# LEDDimmerDuoMini.net
KiCad netlist of a schematic drawn in EAGLE
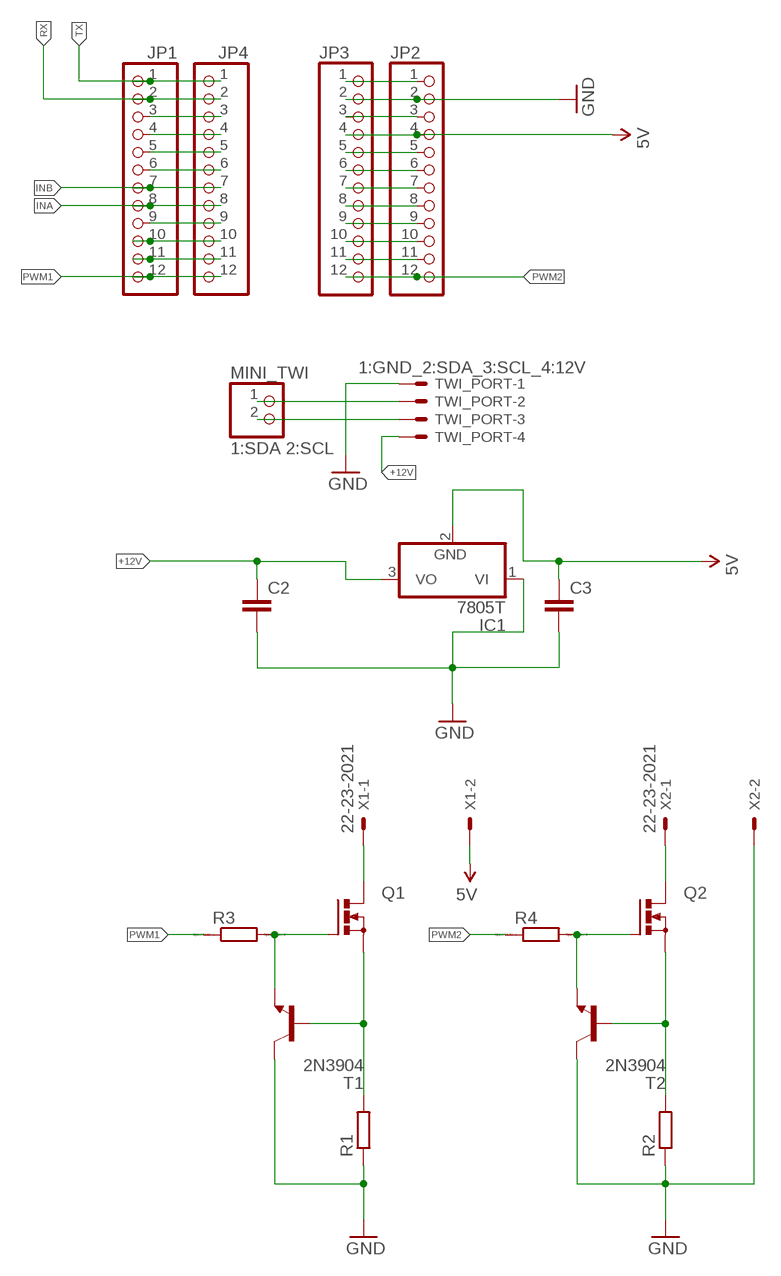
[diagram p0: schematic, sheet 1]

(export (version "E")
  (design (tool "Eeschema 10.0.6"))
  (components
    (comp (ref "C2")
      (value "CAP0603-CAP")
      (footprint "eagle-import:0603-CAP")
      (libsource (lib "eagle-import") (part "CAP0603-CAP"))
    )
    (comp (ref "C3")
      (value "CAP0603-CAP")
      (footprint "eagle-import:0603-CAP")
      (libsource (lib "eagle-import") (part "CAP0603-CAP"))
    )
    (comp (ref "IC1")
      (value "7805T")
      (footprint "eagle-import:TO220H")
      (libsource (lib "eagle-import") (part "78T05"))
    )
    (comp (ref "JP1")
      (value "PINHD-1X12")
      (footprint "eagle-import:1X12")
      (libsource (lib "eagle-import") (part "PINHD-1X12"))
    )
    (comp (ref "JP2")
      (value "PINHD-1X12")
      (footprint "eagle-import:1X12")
      (libsource (lib "eagle-import") (part "PINHD-1X12"))
    )
    (comp (ref "JP3")
      (value "PINHD-1X12")
      (footprint "eagle-import:1X12")
      (libsource (lib "eagle-import") (part "PINHD-1X12"))
    )
    (comp (ref "JP4")
      (value "PINHD-1X12")
      (footprint "eagle-import:1X12")
      (libsource (lib "eagle-import") (part "PINHD-1X12"))
    )
    (comp (ref "MINI_TWI")
      (value "1:SDA 2:SCL")
      (footprint "eagle-import:1X02")
      (libsource (lib "eagle-import") (part "PINHD-1X2"))
    )
    (comp (ref "Q1")
      (value "PMOSFET_NTO220BV")
      (footprint "eagle-import:TO220BV")
      (libsource (lib "eagle-import") (part "PMOSFET_NTO220BV"))
    )
    (comp (ref "Q2")
      (value "PMOSFET_NTO220BV")
      (footprint "eagle-import:TO220BV")
      (libsource (lib "eagle-import") (part "PMOSFET_NTO220BV"))
    )
    (comp (ref "R1")
      (value "R-EU_VTA52")
      (footprint "eagle-import:VTA52")
      (libsource (lib "eagle-import") (part "R-EU_VTA52"))
    )
    (comp (ref "R2")
      (value "R-EU_VTA52")
      (footprint "eagle-import:VTA52")
      (libsource (lib "eagle-import") (part "R-EU_VTA52"))
    )
    (comp (ref "R3") (value "R") (footprint "eagle-import:R0805") (libsource (lib "eagle-import") (part "R")))
    (comp (ref "R4") (value "R") (footprint "eagle-import:R0805") (libsource (lib "eagle-import") (part "R")))
    (comp (ref "T1")
      (value "2N3904")
      (footprint "eagle-import:TO92")
      (libsource (lib "eagle-import") (part "2N3904"))
    )
    (comp (ref "T2")
      (value "2N3904")
      (footprint "eagle-import:TO92")
      (libsource (lib "eagle-import") (part "2N3904"))
    )
    (comp (ref "TWI_PORT")
      (value "1:GND_2:SDA_3:SCL_4:12V")
      (footprint "eagle-import:22-23-2041")
      (fields (field (name "MF") "MOLEX") (field (name "MPN") "22-23-2041"))
      (libsource (lib "eagle-import") (part "22-23-2041"))
    )
    (comp (ref "X1")
      (value "22-23-2021")
      (footprint "eagle-import:22-23-2021")
      (fields (field (name "MF") "MOLEX"))
      (libsource (lib "eagle-import") (part "22-23-2021"))
    )
    (comp (ref "X2")
      (value "22-23-2021")
      (footprint "eagle-import:22-23-2021")
      (fields (field (name "MF") "MOLEX"))
      (libsource (lib "eagle-import") (part "22-23-2021"))
    )
  )
  (nets
    (net (code "1") (name "+12V") (class "Default")
      (node (ref "C2") (pin "1") (pinfunction "1_1") (pintype "passive"))
      (node (ref "IC1") (pin "3") (pinfunction "VO_3") (pintype "passive"))
      (node (ref "TWI_PORT") (pin "4") (pinfunction "S_4") (pintype "passive"))
    )
    (net (code "2") (name "5V") (class "Default")
      (node (ref "C3") (pin "1") (pinfunction "1_1") (pintype "passive"))
      (node (ref "IC1") (pin "2") (pinfunction "GND_2") (pintype "passive"))
      (node (ref "JP2") (pin "4") (pinfunction "4_4") (pintype "passive"))
      (node (ref "JP3") (pin "4") (pinfunction "4_4") (pintype "passive"))
      (node (ref "X1") (pin "2") (pinfunction "S_2") (pintype "passive"))
    )
    (net (code "3") (name "GND") (class "Default")
      (node (ref "C2") (pin "2") (pinfunction "2_2") (pintype "passive"))
      (node (ref "C3") (pin "2") (pinfunction "2_2") (pintype "passive"))
      (node (ref "IC1") (pin "1") (pinfunction "VI_1") (pintype "input"))
      (node (ref "JP2") (pin "2") (pinfunction "2_2") (pintype "passive"))
      (node (ref "JP3") (pin "2") (pinfunction "2_2") (pintype "passive"))
      (node (ref "R1") (pin "1") (pinfunction "1_1") (pintype "passive"))
      (node (ref "R2") (pin "1") (pinfunction "1_1") (pintype "passive"))
      (node (ref "T1") (pin "1") (pinfunction "C_1") (pintype "passive"))
      (node (ref "T2") (pin "1") (pinfunction "C_1") (pintype "passive"))
      (node (ref "TWI_PORT") (pin "1") (pinfunction "S_1") (pintype "passive"))
      (node (ref "X2") (pin "2") (pinfunction "S_2") (pintype "passive"))
    )
    (net (code "4") (name "INA") (class "Default")
      (node (ref "JP1") (pin "8") (pinfunction "8_8") (pintype "passive"))
      (node (ref "JP4") (pin "8") (pinfunction "8_8") (pintype "passive"))
    )
    (net (code "5") (name "INB") (class "Default")
      (node (ref "JP1") (pin "7") (pinfunction "7_7") (pintype "passive"))
      (node (ref "JP4") (pin "7") (pinfunction "7_7") (pintype "passive"))
    )
    (net (code "6") (name "Net-(JP1-Pad3)") (class "Default")
      (node (ref "JP1") (pin "3") (pinfunction "3_3") (pintype "passive"))
      (node (ref "JP4") (pin "3") (pinfunction "3_3") (pintype "passive"))
    )
    (net (code "7") (name "Net-(JP1-Pad4)") (class "Default")
      (node (ref "JP1") (pin "4") (pinfunction "4_4") (pintype "passive"))
      (node (ref "JP4") (pin "4") (pinfunction "4_4") (pintype "passive"))
    )
    (net (code "8") (name "Net-(JP1-Pad5)") (class "Default")
      (node (ref "JP1") (pin "5") (pinfunction "5_5") (pintype "passive"))
      (node (ref "JP4") (pin "5") (pinfunction "5_5") (pintype "passive"))
    )
    (net (code "9") (name "Net-(JP1-Pad6)") (class "Default")
      (node (ref "JP1") (pin "6") (pinfunction "6_6") (pintype "passive"))
      (node (ref "JP4") (pin "6") (pinfunction "6_6") (pintype "passive"))
    )
    (net (code "10") (name "Net-(JP1-Pad9)") (class "Default")
      (node (ref "JP1") (pin "9") (pinfunction "9_9") (pintype "passive"))
      (node (ref "JP4") (pin "9") (pinfunction "9_9") (pintype "passive"))
    )
    (net (code "11") (name "Net-(JP1-Pad10)") (class "Default")
      (node (ref "JP1") (pin "10") (pinfunction "10_10") (pintype "passive"))
      (node (ref "JP4") (pin "10") (pinfunction "10_10") (pintype "passive"))
    )
    (net (code "12") (name "Net-(JP1-Pad11)") (class "Default")
      (node (ref "JP1") (pin "11") (pinfunction "11_11") (pintype "passive"))
      (node (ref "JP4") (pin "11") (pinfunction "11_11") (pintype "passive"))
    )
    (net (code "13") (name "Net-(JP2-Pad1)") (class "Default")
      (node (ref "JP2") (pin "1") (pinfunction "1_1") (pintype "passive"))
      (node (ref "JP3") (pin "1") (pinfunction "1_1") (pintype "passive"))
    )
    (net (code "14") (name "Net-(JP2-Pad3)") (class "Default")
      (node (ref "JP2") (pin "3") (pinfunction "3_3") (pintype "passive"))
      (node (ref "JP3") (pin "3") (pinfunction "3_3") (pintype "passive"))
    )
    (net (code "15") (name "Net-(JP2-Pad5)") (class "Default")
      (node (ref "JP2") (pin "5") (pinfunction "5_5") (pintype "passive"))
      (node (ref "JP3") (pin "5") (pinfunction "5_5") (pintype "passive"))
    )
    (net (code "16") (name "Net-(JP2-Pad6)") (class "Default")
      (node (ref "JP2") (pin "6") (pinfunction "6_6") (pintype "passive"))
      (node (ref "JP3") (pin "6") (pinfunction "6_6") (pintype "passive"))
    )
    (net (code "17") (name "Net-(JP2-Pad7)") (class "Default")
      (node (ref "JP2") (pin "7") (pinfunction "7_7") (pintype "passive"))
      (node (ref "JP3") (pin "7") (pinfunction "7_7") (pintype "passive"))
    )
    (net (code "18") (name "Net-(JP2-Pad8)") (class "Default")
      (node (ref "JP2") (pin "8") (pinfunction "8_8") (pintype "passive"))
      (node (ref "JP3") (pin "8") (pinfunction "8_8") (pintype "passive"))
    )
    (net (code "19") (name "Net-(JP2-Pad9)") (class "Default")
      (node (ref "JP2") (pin "9") (pinfunction "9_9") (pintype "passive"))
      (node (ref "JP3") (pin "9") (pinfunction "9_9") (pintype "passive"))
    )
    (net (code "20") (name "Net-(JP2-Pad10)") (class "Default")
      (node (ref "JP2") (pin "10") (pinfunction "10_10") (pintype "passive"))
      (node (ref "JP3") (pin "10") (pinfunction "10_10") (pintype "passive"))
    )
    (net (code "21") (name "Net-(JP2-Pad11)") (class "Default")
      (node (ref "JP2") (pin "11") (pinfunction "11_11") (pintype "passive"))
      (node (ref "JP3") (pin "11") (pinfunction "11_11") (pintype "passive"))
    )
    (net (code "22") (name "Net-(T1-B)") (class "Default")
      (node (ref "Q1") (pin "S") (pinfunction "S_S") (pintype "passive"))
      (node (ref "R1") (pin "2") (pinfunction "2_2") (pintype "passive"))
      (node (ref "T1") (pin "2") (pinfunction "B_2") (pintype "passive"))
    )
    (net (code "23") (name "Net-(T2-B)") (class "Default")
      (node (ref "Q2") (pin "S") (pinfunction "S_S") (pintype "passive"))
      (node (ref "R2") (pin "2") (pinfunction "2_2") (pintype "passive"))
      (node (ref "T2") (pin "2") (pinfunction "B_2") (pintype "passive"))
    )
    (net (code "24") (name "Net-(T2-E)") (class "Default")
      (node (ref "Q2") (pin "G") (pinfunction "G_G") (pintype "passive"))
      (node (ref "R4") (pin "2") (pinfunction "2_2") (pintype "passive"))
      (node (ref "T2") (pin "3") (pinfunction "E_3") (pintype "passive"))
    )
    (net (code "25") (name "Net-(TWI_PORTB-S)") (class "Default")
      (node (ref "MINI_TWI") (pin "1") (pinfunction "1_1") (pintype "passive"))
      (node (ref "TWI_PORT") (pin "2") (pinfunction "S_2") (pintype "passive"))
    )
    (net (code "26") (name "Net-(TWI_PORTC-S)") (class "Default")
      (node (ref "MINI_TWI") (pin "2") (pinfunction "2_2") (pintype "passive"))
      (node (ref "TWI_PORT") (pin "3") (pinfunction "S_3") (pintype "passive"))
    )
    (net (code "27") (name "Net-(X1A-S)") (class "Default")
      (node (ref "Q1") (pin "D") (pinfunction "D_D") (pintype "passive"))
      (node (ref "X1") (pin "1") (pinfunction "S_1") (pintype "passive"))
    )
    (net (code "28") (name "Net-(X2A-S)") (class "Default")
      (node (ref "Q2") (pin "D") (pinfunction "D_D") (pintype "passive"))
      (node (ref "X2") (pin "1") (pinfunction "S_1") (pintype "passive"))
    )
    (net (code "29") (name "PWM1") (class "Default")
      (node (ref "JP1") (pin "12") (pinfunction "12_12") (pintype "passive"))
      (node (ref "JP4") (pin "12") (pinfunction "12_12") (pintype "passive"))
      (node (ref "Q1") (pin "G") (pinfunction "G_G") (pintype "passive"))
      (node (ref "R3") (pin "1") (pinfunction "1_1") (pintype "passive"))
      (node (ref "R3") (pin "2") (pinfunction "2_2") (pintype "passive"))
      (node (ref "T1") (pin "3") (pinfunction "E_3") (pintype "passive"))
    )
    (net (code "30") (name "PWM2") (class "Default")
      (node (ref "JP2") (pin "12") (pinfunction "12_12") (pintype "passive"))
      (node (ref "JP3") (pin "12") (pinfunction "12_12") (pintype "passive"))
      (node (ref "R4") (pin "1") (pinfunction "1_1") (pintype "passive"))
    )
    (net (code "31") (name "RX") (class "Default")
      (node (ref "JP1") (pin "2") (pinfunction "2_2") (pintype "passive"))
      (node (ref "JP4") (pin "2") (pinfunction "2_2") (pintype "passive"))
    )
    (net (code "32") (name "TX") (class "Default")
      (node (ref "JP1") (pin "1") (pinfunction "1_1") (pintype "passive"))
      (node (ref "JP4") (pin "1") (pinfunction "1_1") (pintype "passive"))
    )
  )
)
